# programming_jig.net
KiCad netlist of a schematic drawn in EasyEDA Pro
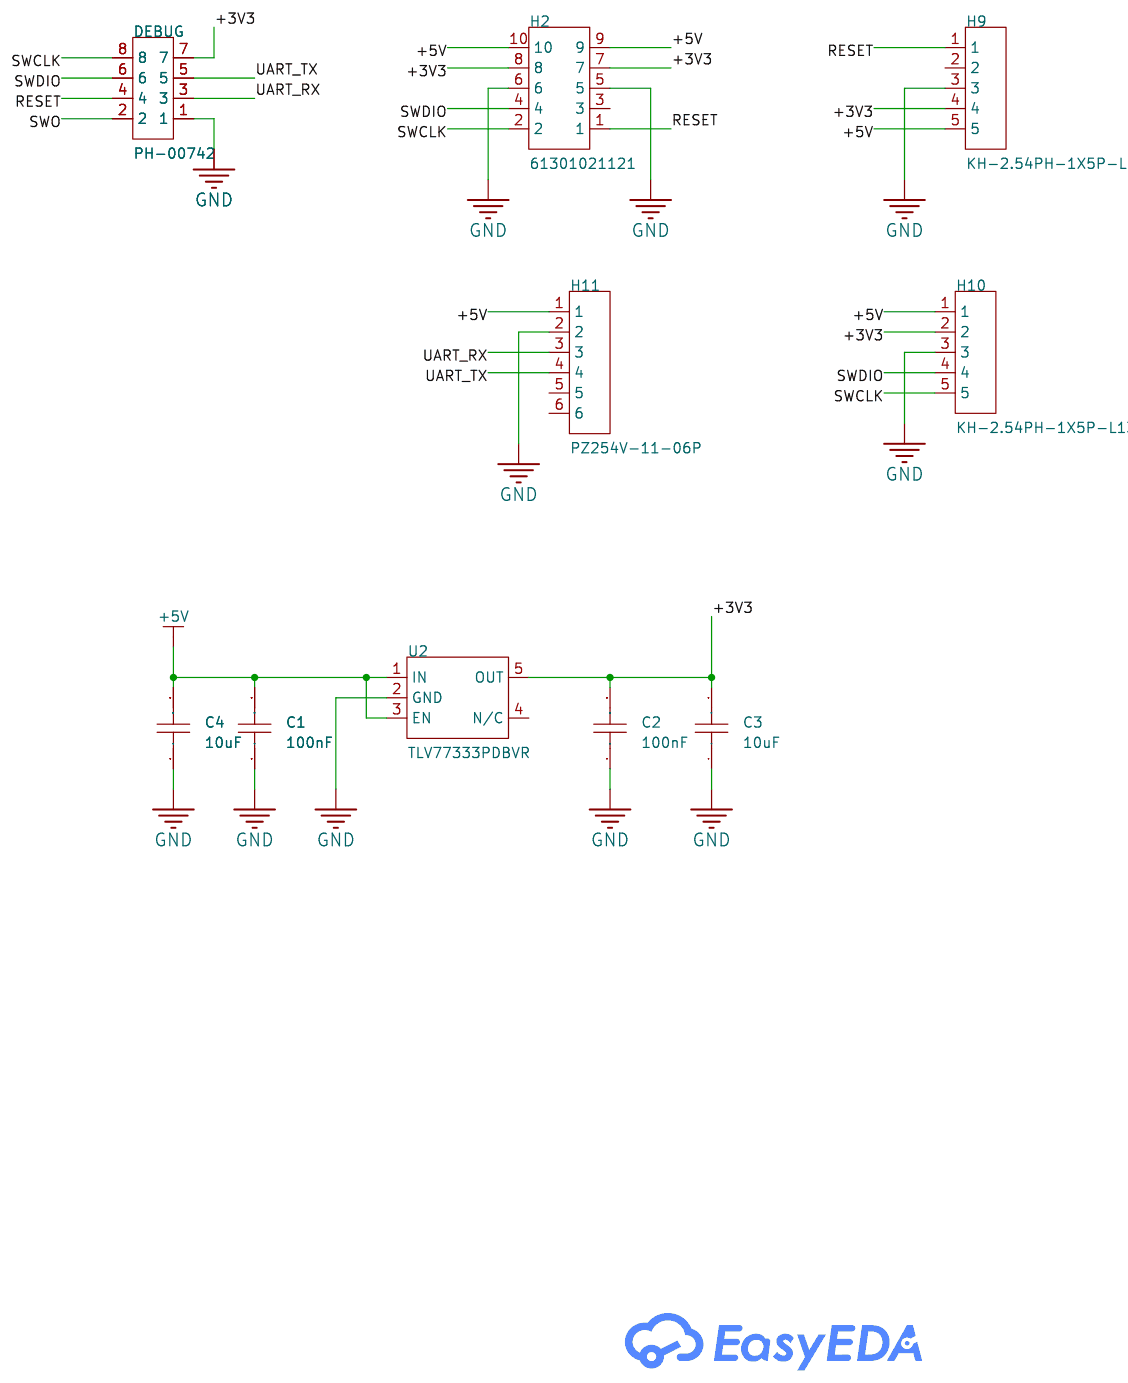
[diagram p0: schematic sheet]

(export (version "E")
  (design (tool "Eeschema 10.0.6"))
  (components
    (comp (ref "C1")
      (value "100nF")
      (footprint "easyedapro:C0805")
      (description "Capacitance:100nF Tolerance:±10% Tolerance:±10% Voltage Rating:50V Temperature Coefficient:X7R")
      (fields
        (field (name "Manufacturer Part") "CC0805KRX7R9BB104")
        (field (name "Manufacturer") "YAGEO(国巨)")
      )
      (libsource (lib "easyedapro") (part "CC0805KRX7R9BB104"))
    )
    (comp (ref "C2")
      (value "100nF")
      (footprint "easyedapro:C0805")
      (description "Capacitance:100nF Tolerance:±10% Tolerance:±10% Voltage Rating:50V Temperature Coefficient:X7R")
      (fields
        (field (name "Manufacturer Part") "CC0805KRX7R9BB104")
        (field (name "Manufacturer") "YAGEO(国巨)")
      )
      (libsource (lib "easyedapro") (part "CC0805KRX7R9BB104"))
    )
    (comp (ref "C3")
      (value "10uF")
      (footprint "easyedapro:C0805")
      (description "Capacitance:10uF Tolerance:±10% Tolerance:±10% Voltage Rating:50V Temperature Coefficient:X5R")
      (fields
        (field (name "Manufacturer Part") "GRM21BR61H106KE43L")
        (field (name "Manufacturer") "muRata(村田)")
      )
      (libsource (lib "easyedapro") (part "GRM21BR61H106KE43L"))
    )
    (comp (ref "C4")
      (value "10uF")
      (footprint "easyedapro:C0805")
      (description "Capacitance:10uF Tolerance:±10% Tolerance:±10% Voltage Rating:50V Temperature Coefficient:X5R")
      (fields
        (field (name "Manufacturer Part") "GRM21BR61H106KE43L")
        (field (name "Manufacturer") "muRata(村田)")
      )
      (libsource (lib "easyedapro") (part "GRM21BR61H106KE43L"))
    )
    (comp (ref "DEBUG")
      (value "PH-00742")
      (footprint "easyedapro:HDR-TH_8P-P1.27-V-M-R2-C4-S1.27")
      (fields (field (name "Manufacturer") "Liansheng(连盛)"))
      (libsource (lib "easyedapro") (part "PH-00742"))
    )
    (comp (ref "H2")
      (value "61301021121")
      (footprint "easyedapro:HDR-TH_10P-P2.54-V-M-R2-C5-S2.54")
      (fields (field (name "Manufacturer") "Wurth(伍尔特)"))
      (libsource (lib "easyedapro") (part "61301021121"))
    )
    (comp (ref "H9")
      (value "KH-2.54PH-1X5P-L13.5-WT")
      (footprint "easyedapro:HDR-SMD_5P-P2.54_KH-2.54PH-1X5P-L13.5-WT")
      (fields (field (name "Manufacturer") "kinghelm(金航标)"))
      (libsource (lib "easyedapro") (part "KH-2.54PH-1X5P-L13.5-WT"))
    )
    (comp (ref "H10")
      (value "KH-2.54PH-1X5P-L13.5-WT")
      (footprint "easyedapro:HDR-SMD_5P-P2.54_KH-2.54PH-1X5P-L13.5-WT")
      (fields (field (name "Manufacturer") "kinghelm(金航标)"))
      (libsource (lib "easyedapro") (part "KH-2.54PH-1X5P-L13.5-WT"))
    )
    (comp (ref "H11")
      (value "PZ254V-11-06P")
      (footprint "easyedapro:HDR-TH_6P-P2.54-V-M")
      (fields (field (name "Manufacturer") "XFCN(兴飞)"))
      (libsource (lib "easyedapro") (part "PZ254V-11-06P"))
    )
    (comp (ref "U2")
      (value "TLV77333PDBVR")
      (footprint "easyedapro:SOT-23-5_L2.9-W1.6-P0.95-LS2.8-BR")
      (fields (field (name "Manufacturer") "TI(德州仪器)"))
      (libsource (lib "easyedapro") (part "TLV77333PDBVR"))
    )
  )
  (nets
    (net (code "1") (name "+5V") (class "Default")
      (node (ref "C1") (pin "2") (pinfunction "2_2") (pintype "unspecified"))
      (node (ref "C4") (pin "2") (pinfunction "2_2") (pintype "unspecified"))
      (node (ref "H10") (pin "1") (pinfunction "1_1") (pintype "unspecified"))
      (node (ref "H11") (pin "1") (pinfunction "1_1") (pintype "unspecified"))
      (node (ref "H2") (pin "10") (pinfunction "10_10") (pintype "unspecified"))
      (node (ref "H2") (pin "9") (pinfunction "9_9") (pintype "unspecified"))
      (node (ref "H9") (pin "5") (pinfunction "5_5") (pintype "unspecified"))
      (node (ref "U2") (pin "1") (pinfunction "IN_1") (pintype "unspecified"))
      (node (ref "U2") (pin "3") (pinfunction "EN_3") (pintype "unspecified"))
    )
    (net (code "2") (name "/+3V3") (class "Default")
      (node (ref "C2") (pin "2") (pinfunction "2_2") (pintype "unspecified"))
      (node (ref "C3") (pin "2") (pinfunction "2_2") (pintype "unspecified"))
      (node (ref "DEBUG") (pin "7") (pinfunction "7_7") (pintype "unspecified"))
      (node (ref "H10") (pin "2") (pinfunction "2_2") (pintype "unspecified"))
      (node (ref "H2") (pin "7") (pinfunction "7_7") (pintype "unspecified"))
      (node (ref "H2") (pin "8") (pinfunction "8_8") (pintype "unspecified"))
      (node (ref "H9") (pin "4") (pinfunction "4_4") (pintype "unspecified"))
      (node (ref "U2") (pin "5") (pinfunction "OUT_5") (pintype "unspecified"))
    )
    (net (code "3") (name "/RESET") (class "Default")
      (node (ref "DEBUG") (pin "4") (pinfunction "4_4") (pintype "unspecified"))
      (node (ref "H2") (pin "1") (pinfunction "1_1") (pintype "unspecified"))
      (node (ref "H9") (pin "1") (pinfunction "1_1") (pintype "unspecified"))
    )
    (net (code "4") (name "/SWCLK") (class "Default")
      (node (ref "DEBUG") (pin "8") (pinfunction "8_8") (pintype "unspecified"))
      (node (ref "H10") (pin "5") (pinfunction "5_5") (pintype "unspecified"))
      (node (ref "H2") (pin "2") (pinfunction "2_2") (pintype "unspecified"))
    )
    (net (code "5") (name "/SWDIO") (class "Default")
      (node (ref "DEBUG") (pin "6") (pinfunction "6_6") (pintype "unspecified"))
      (node (ref "H10") (pin "4") (pinfunction "4_4") (pintype "unspecified"))
      (node (ref "H2") (pin "4") (pinfunction "4_4") (pintype "unspecified"))
    )
    (net (code "6") (name "/SWO") (class "Default")
      (node (ref "DEBUG") (pin "2") (pinfunction "2_2") (pintype "unspecified"))
    )
    (net (code "7") (name "/UART_RX") (class "Default")
      (node (ref "DEBUG") (pin "3") (pinfunction "3_3") (pintype "unspecified"))
      (node (ref "H11") (pin "3") (pinfunction "3_3") (pintype "unspecified"))
    )
    (net (code "8") (name "/UART_TX") (class "Default")
      (node (ref "DEBUG") (pin "5") (pinfunction "5_5") (pintype "unspecified"))
      (node (ref "H11") (pin "4") (pinfunction "4_4") (pintype "unspecified"))
    )
    (net (code "9") (name "GND") (class "Default")
      (node (ref "C1") (pin "1") (pinfunction "1_1") (pintype "unspecified"))
      (node (ref "C2") (pin "1") (pinfunction "1_1") (pintype "unspecified"))
      (node (ref "C3") (pin "1") (pinfunction "1_1") (pintype "unspecified"))
      (node (ref "C4") (pin "1") (pinfunction "1_1") (pintype "unspecified"))
      (node (ref "DEBUG") (pin "1") (pinfunction "1_1") (pintype "unspecified"))
      (node (ref "H10") (pin "3") (pinfunction "3_3") (pintype "unspecified"))
      (node (ref "H11") (pin "2") (pinfunction "2_2") (pintype "unspecified"))
      (node (ref "H2") (pin "5") (pinfunction "5_5") (pintype "unspecified"))
      (node (ref "H2") (pin "6") (pinfunction "6_6") (pintype "unspecified"))
      (node (ref "H9") (pin "3") (pinfunction "3_3") (pintype "unspecified"))
      (node (ref "U2") (pin "2") (pinfunction "GND_2") (pintype "unspecified"))
    )
    (net (code "10") (name "unconnected-(H2-Pad3)") (class "Default")
      (node (ref "H2") (pin "3") (pinfunction "3_3") (pintype "unspecified"))
    )
    (net (code "11") (name "unconnected-(H9-Pad2)") (class "Default")
      (node (ref "H9") (pin "2") (pinfunction "2_2") (pintype "unspecified"))
    )
    (net (code "12") (name "unconnected-(H11-Pad5)") (class "Default")
      (node (ref "H11") (pin "5") (pinfunction "5_5") (pintype "unspecified"))
    )
    (net (code "13") (name "unconnected-(H11-Pad6)") (class "Default")
      (node (ref "H11") (pin "6") (pinfunction "6_6") (pintype "unspecified"))
    )
    (net (code "14") (name "unconnected-(U2-N{slash}C-Pad4)") (class "Default")
      (node (ref "U2") (pin "4") (pinfunction "N/C_4") (pintype "unspecified"))
    )
  )
)
